# Tiny_Programmer_v11.net
KiCad netlist of a schematic drawn in EAGLE
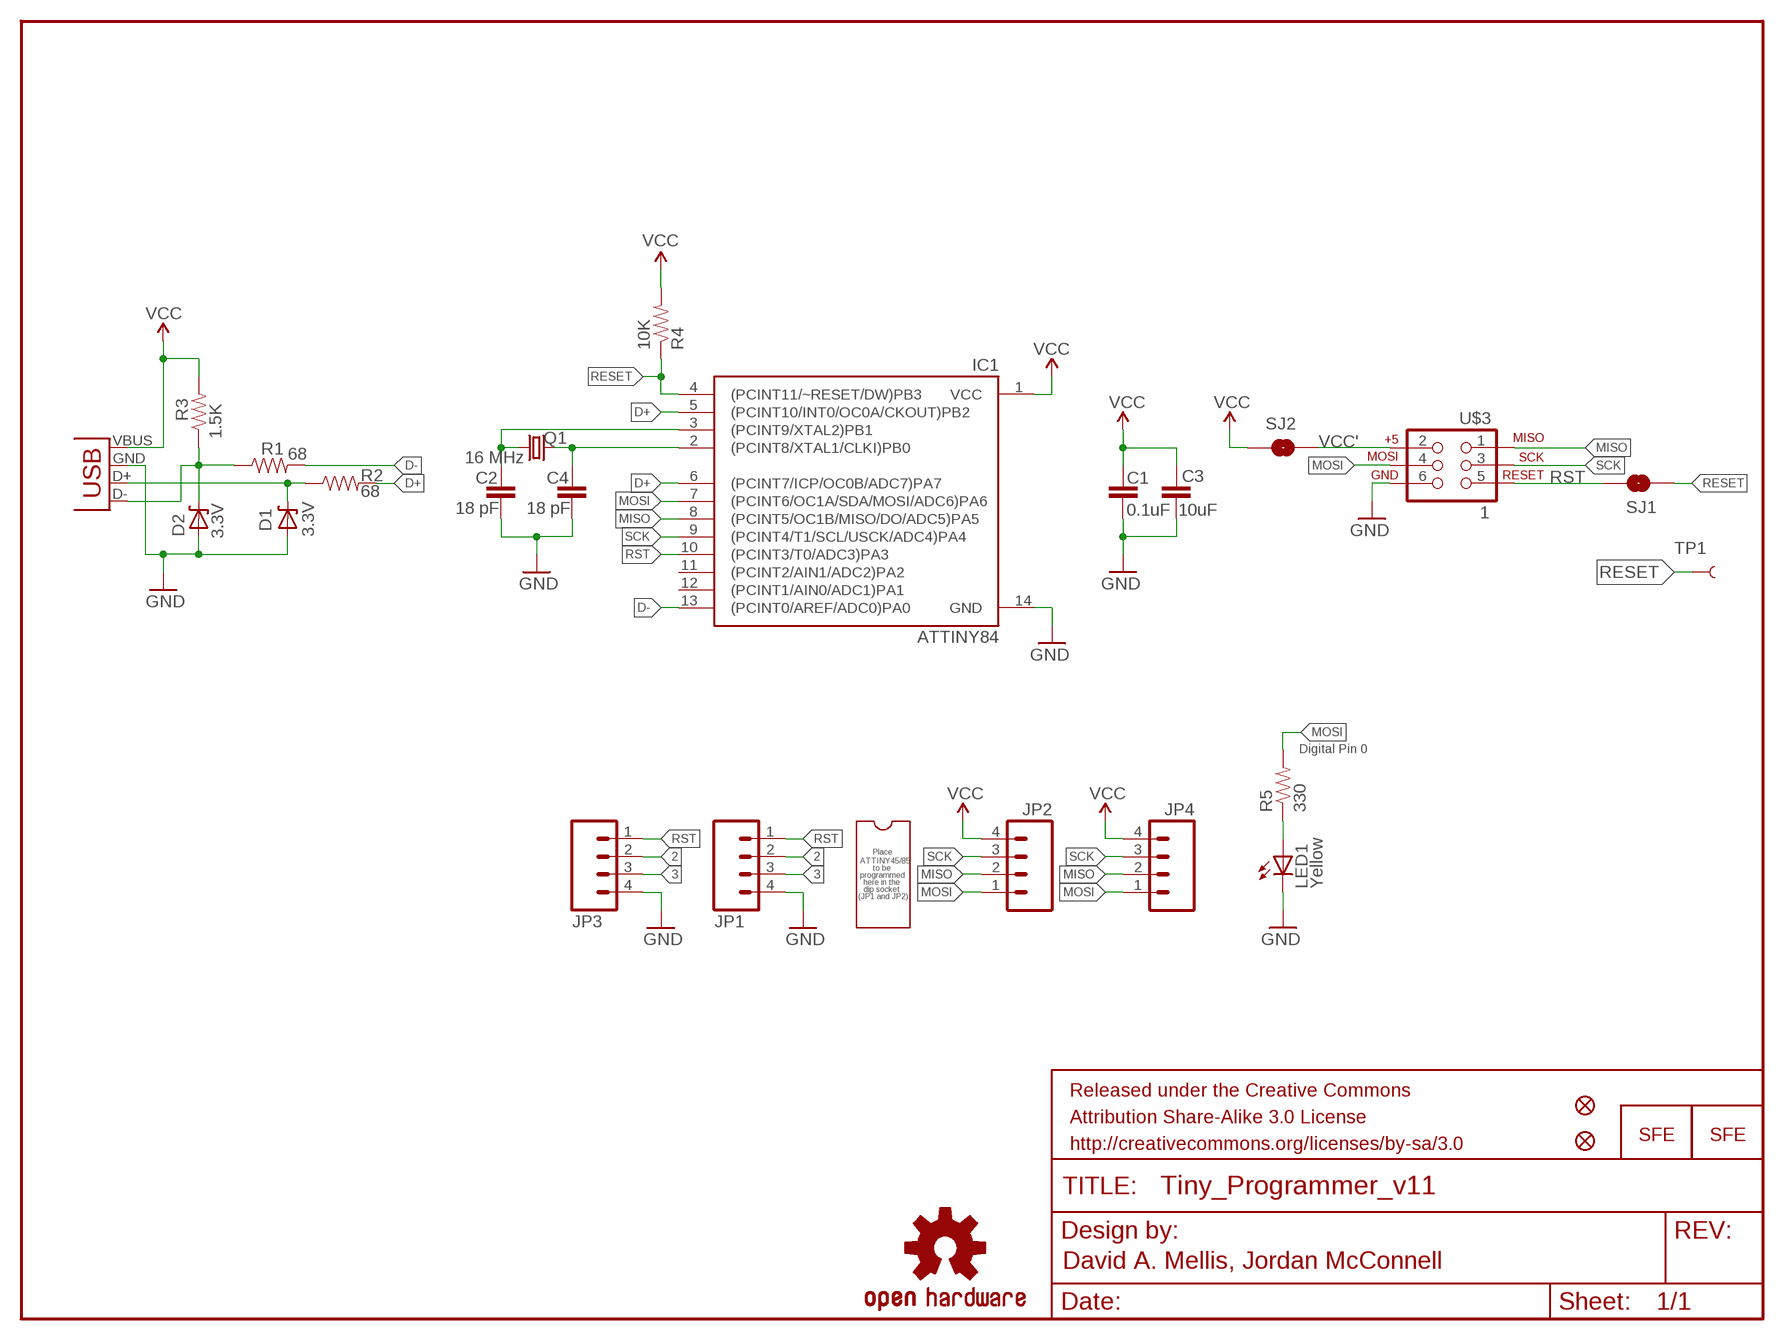
[diagram p0: schematic, sheet 1]

(export (version "E")
  (design (tool "Eeschema 10.0.6"))
  (components
    (comp (ref "C1")
      (value "0.1uF")
      (footprint "eagle-import:0402-CAP")
      (libsource (lib "eagle-import") (part "CAP0402-CAP"))
    )
    (comp (ref "C2")
      (value "18 pF")
      (footprint "eagle-import:0402-CAP")
      (libsource (lib "eagle-import") (part "CAP0402-CAP"))
    )
    (comp (ref "C3")
      (value "10uF")
      (footprint "eagle-import:0402-CAP")
      (libsource (lib "eagle-import") (part "CAP0402-CAP"))
    )
    (comp (ref "C4")
      (value "18 pF")
      (footprint "eagle-import:0402-CAP")
      (libsource (lib "eagle-import") (part "CAP0402-CAP"))
    )
    (comp (ref "D1")
      (value "3.3V")
      (footprint "eagle-import:SOD-323")
      (libsource (lib "eagle-import") (part "DIODE-ZENER-BZT52"))
    )
    (comp (ref "D2")
      (value "3.3V")
      (footprint "eagle-import:SOD-323")
      (libsource (lib "eagle-import") (part "DIODE-ZENER-BZT52"))
    )
    (comp (ref "FRAME1")
      (value "FRAME-LETTER")
      (footprint "eagle-import:CREATIVE_COMMONS")
      (libsource (lib "eagle-import") (part "FRAME-LETTER"))
    )
    (comp (ref "IC1")
      (value "ATTINY84")
      (footprint "eagle-import:SO14")
      (libsource (lib "eagle-import") (part "ATTINY84"))
    )
    (comp (ref "JP1")
      (value "M04PTH")
      (footprint "eagle-import:1X04")
      (libsource (lib "eagle-import") (part "M04PTH"))
    )
    (comp (ref "JP2")
      (value "M04PTH")
      (footprint "eagle-import:1X04")
      (libsource (lib "eagle-import") (part "M04PTH"))
    )
    (comp (ref "JP3")
      (value "M04SMD_STRAIGHT_COMBO")
      (footprint "eagle-import:1X04_SMD_STRAIGHT_COMBO")
      (libsource (lib "eagle-import") (part "M04SMD_STRAIGHT_COMBO"))
    )
    (comp (ref "JP4")
      (value "M04SMD_STRAIGHT_COMBO")
      (footprint "eagle-import:1X04_SMD_STRAIGHT_COMBO")
      (libsource (lib "eagle-import") (part "M04SMD_STRAIGHT_COMBO"))
    )
    (comp (ref "JP5")
      (value "LOGO-SFENEW")
      (footprint "eagle-import:SFE-NEW-WEBLOGO")
      (libsource (lib "eagle-import") (part "LOGO-SFENEW"))
    )
    (comp (ref "JP6")
      (value "LOGO-SFESK")
      (footprint "eagle-import:SFE-LOGO-FLAME")
      (libsource (lib "eagle-import") (part "LOGO-SFESK"))
    )
    (comp (ref "JP7")
      (value "FIDUCIALUFIDUCIAL")
      (footprint "eagle-import:MICRO-FIDUCIAL")
      (libsource (lib "eagle-import") (part "FIDUCIALUFIDUCIAL"))
    )
    (comp (ref "JP8")
      (value "FIDUCIALUFIDUCIAL")
      (footprint "eagle-import:MICRO-FIDUCIAL")
      (libsource (lib "eagle-import") (part "FIDUCIALUFIDUCIAL"))
    )
    (comp (ref "LED1")
      (value "Yellow")
      (footprint "eagle-import:LED-0603")
      (libsource (lib "eagle-import") (part "LED0603"))
    )
    (comp (ref "Q1")
      (value "16 MHz")
      (footprint "eagle-import:CRYSTAL-SMD-5X3")
      (libsource (lib "eagle-import") (part "CRYSTAL5X3"))
    )
    (comp (ref "R1")
      (value "68")
      (footprint "eagle-import:0402-RES")
      (libsource (lib "eagle-import") (part "RESISTOR0402-RES"))
    )
    (comp (ref "R2")
      (value "68")
      (footprint "eagle-import:0402-RES")
      (libsource (lib "eagle-import") (part "RESISTOR0402-RES"))
    )
    (comp (ref "R3")
      (value "1.5K")
      (footprint "eagle-import:0402-RES")
      (libsource (lib "eagle-import") (part "RESISTOR0402-RES"))
    )
    (comp (ref "R4")
      (value "10K")
      (footprint "eagle-import:0402-RES")
      (libsource (lib "eagle-import") (part "RESISTOR0402-RES"))
    )
    (comp (ref "R5")
      (value "330")
      (footprint "eagle-import:0402-RES")
      (libsource (lib "eagle-import") (part "RESISTOR0402-RES"))
    )
    (comp (ref "SJ1")
      (value "SOLDERJUMPERNO")
      (footprint "eagle-import:SJ_2S-NO")
      (libsource (lib "eagle-import") (part "SOLDERJUMPERNO"))
    )
    (comp (ref "SJ2")
      (value "SOLDERJUMPERNC")
      (footprint "eagle-import:SJ_2S")
      (libsource (lib "eagle-import") (part "SOLDERJUMPERNC"))
    )
    (comp (ref "TP1")
      (value "TEST-POINT3")
      (footprint "eagle-import:PAD.03X.03")
      (libsource (lib "eagle-import") (part "TEST-POINT3"))
    )
    (comp (ref "U$1")
      (value "OSHW-LOGOS")
      (footprint "eagle-import:OSHW-LOGO-S")
      (libsource (lib "eagle-import") (part "OSHW-LOGOS"))
    )
    (comp (ref "U$3")
      (value "1")
      (footprint "eagle-import:2X3")
      (libsource (lib "eagle-import") (part "AVR_SPI_PRG_6PTH"))
    )
    (comp (ref "X1")
      (value "USB-A-H")
      (footprint "eagle-import:USB-A-H")
      (libsource (lib "eagle-import") (part "USB-A-H"))
    )
  )
  (nets
    (net (code "1") (name "/VCC'") (class "Default")
      (node (ref "SJ2") (pin "2") (pinfunction "2_2") (pintype "passive"))
      (node (ref "U$3") (pin "2") (pinfunction "2_2") (pintype "passive"))
    )
    (net (code "2") (name "2") (class "Default")
      (node (ref "JP1") (pin "2") (pinfunction "2_2") (pintype "passive"))
      (node (ref "JP3") (pin "2") (pinfunction "2_2") (pintype "passive"))
    )
    (net (code "3") (name "3") (class "Default")
      (node (ref "JP1") (pin "3") (pinfunction "3_3") (pintype "passive"))
      (node (ref "JP3") (pin "3") (pinfunction "3_3") (pintype "passive"))
    )
    (net (code "4") (name "D+") (class "Default")
      (node (ref "IC1") (pin "5") (pinfunction "(PCINT10/INT0/OC0A/CKOUT)PB2_5") (pintype "bidirectional"))
      (node (ref "IC1") (pin "6") (pinfunction "(PCINT7/ICP/OC0B/ADC7)PA7_6") (pintype "bidirectional"))
      (node (ref "R2") (pin "2") (pinfunction "2_2") (pintype "passive"))
    )
    (net (code "5") (name "D-") (class "Default")
      (node (ref "IC1") (pin "13") (pinfunction "(PCINT0/AREF/ADC0)PA0_13") (pintype "bidirectional"))
      (node (ref "R1") (pin "2") (pinfunction "2_2") (pintype "passive"))
    )
    (net (code "6") (name "GND") (class "Default")
      (node (ref "C1") (pin "2") (pinfunction "2_2") (pintype "passive"))
      (node (ref "C2") (pin "2") (pinfunction "2_2") (pintype "passive"))
      (node (ref "C3") (pin "2") (pinfunction "2_2") (pintype "passive"))
      (node (ref "C4") (pin "2") (pinfunction "2_2") (pintype "passive"))
      (node (ref "D1") (pin "2") (pinfunction "A_2") (pintype "passive"))
      (node (ref "D2") (pin "2") (pinfunction "A_2") (pintype "passive"))
      (node (ref "IC1") (pin "14") (pinfunction "GND_14") (pintype "bidirectional"))
      (node (ref "JP1") (pin "4") (pinfunction "4_4") (pintype "passive"))
      (node (ref "JP3") (pin "4") (pinfunction "4_4") (pintype "passive"))
      (node (ref "LED1") (pin "C") (pinfunction "C_C") (pintype "passive"))
      (node (ref "U$3") (pin "6") (pinfunction "6_6") (pintype "passive"))
      (node (ref "X1") (pin "GND") (pinfunction "VBUS_GND") (pintype "bidirectional"))
    )
    (net (code "7") (name "MISO") (class "Default")
      (node (ref "IC1") (pin "8") (pinfunction "(PCINT5/OC1B/MISO/DO/ADC5)PA5_8") (pintype "bidirectional"))
      (node (ref "JP2") (pin "2") (pinfunction "2_2") (pintype "passive"))
      (node (ref "JP4") (pin "2") (pinfunction "2_2") (pintype "passive"))
      (node (ref "U$3") (pin "1") (pinfunction "1_1") (pintype "passive"))
    )
    (net (code "8") (name "MOSI") (class "Default")
      (node (ref "IC1") (pin "7") (pinfunction "(PCINT6/OC1A/SDA/MOSI/ADC6)PA6_7") (pintype "bidirectional"))
      (node (ref "JP2") (pin "1") (pinfunction "1_1") (pintype "passive"))
      (node (ref "JP4") (pin "1") (pinfunction "1_1") (pintype "passive"))
      (node (ref "R5") (pin "2") (pinfunction "2_2") (pintype "passive"))
      (node (ref "U$3") (pin "4") (pinfunction "4_4") (pintype "passive"))
    )
    (net (code "9") (name "Net-(D1-C)") (class "Default")
      (node (ref "D1") (pin "1") (pinfunction "C_1") (pintype "passive"))
      (node (ref "R2") (pin "1") (pinfunction "1_1") (pintype "passive"))
      (node (ref "X1") (pin "D+") (pinfunction "D-_D+") (pintype "bidirectional"))
    )
    (net (code "10") (name "Net-(D2-C)") (class "Default")
      (node (ref "D2") (pin "1") (pinfunction "C_1") (pintype "passive"))
      (node (ref "R1") (pin "1") (pinfunction "1_1") (pintype "passive"))
      (node (ref "R3") (pin "1") (pinfunction "1_1") (pintype "passive"))
      (node (ref "X1") (pin "D-") (pinfunction "D+_D-") (pintype "bidirectional"))
    )
    (net (code "11") (name "Net-(IC1-(PCINT8{slash}XTAL1{slash}CLKI)PB0)") (class "Default")
      (node (ref "C4") (pin "1") (pinfunction "1_1") (pintype "passive"))
      (node (ref "IC1") (pin "2") (pinfunction "(PCINT8/XTAL1/CLKI)PB0_2") (pintype "bidirectional"))
      (node (ref "Q1") (pin "1") (pinfunction "1_1") (pintype "passive"))
    )
    (net (code "12") (name "Net-(IC1-(PCINT9{slash}XTAL2)PB1)") (class "Default")
      (node (ref "C2") (pin "1") (pinfunction "1_1") (pintype "passive"))
      (node (ref "IC1") (pin "3") (pinfunction "(PCINT9/XTAL2)PB1_3") (pintype "bidirectional"))
      (node (ref "Q1") (pin "3") (pinfunction "2_3") (pintype "passive"))
    )
    (net (code "13") (name "Net-(LED1-PadA)") (class "Default")
      (node (ref "LED1") (pin "A") (pinfunction "A_A") (pintype "passive"))
      (node (ref "R5") (pin "1") (pinfunction "1_1") (pintype "passive"))
    )
    (net (code "14") (name "RESET") (class "Default")
      (node (ref "IC1") (pin "4") (pinfunction "(PCINT11/~{RESET/DW})PB3_4") (pintype "bidirectional"))
      (node (ref "R4") (pin "1") (pinfunction "1_1") (pintype "passive"))
      (node (ref "SJ1") (pin "1") (pinfunction "1_1") (pintype "passive"))
      (node (ref "TP1") (pin "P$1") (pinfunction "1_P$1") (pintype "bidirectional"))
    )
    (net (code "15") (name "RST") (class "Default")
      (node (ref "IC1") (pin "10") (pinfunction "(PCINT3/T0/ADC3)PA3_10") (pintype "bidirectional"))
      (node (ref "JP1") (pin "1") (pinfunction "1_1") (pintype "passive"))
      (node (ref "JP3") (pin "1") (pinfunction "1_1") (pintype "passive"))
      (node (ref "SJ1") (pin "2") (pinfunction "2_2") (pintype "passive"))
      (node (ref "U$3") (pin "5") (pinfunction "5_5") (pintype "passive"))
    )
    (net (code "16") (name "SCK") (class "Default")
      (node (ref "IC1") (pin "9") (pinfunction "(PCINT4/T1/SCL/USCK/ADC4)PA4_9") (pintype "bidirectional"))
      (node (ref "JP2") (pin "3") (pinfunction "3_3") (pintype "passive"))
      (node (ref "JP4") (pin "3") (pinfunction "3_3") (pintype "passive"))
      (node (ref "U$3") (pin "3") (pinfunction "3_3") (pintype "passive"))
    )
    (net (code "17") (name "VCC") (class "Default")
      (node (ref "C1") (pin "1") (pinfunction "1_1") (pintype "passive"))
      (node (ref "C3") (pin "1") (pinfunction "1_1") (pintype "passive"))
      (node (ref "IC1") (pin "1") (pinfunction "VCC_1") (pintype "bidirectional"))
      (node (ref "JP2") (pin "4") (pinfunction "4_4") (pintype "passive"))
      (node (ref "JP4") (pin "4") (pinfunction "4_4") (pintype "passive"))
      (node (ref "R3") (pin "2") (pinfunction "2_2") (pintype "passive"))
      (node (ref "R4") (pin "2") (pinfunction "2_2") (pintype "passive"))
      (node (ref "SJ2") (pin "1") (pinfunction "1_1") (pintype "passive"))
      (node (ref "X1") (pin "VBUS") (pinfunction "GND_VBUS") (pintype "bidirectional"))
    )
    (net (code "18") (name "unconnected-(IC1-(PCINT1{slash}AIN0{slash}ADC1)PA1-Pad12)") (class "Default")
      (node (ref "IC1") (pin "12") (pinfunction "(PCINT1/AIN0/ADC1)PA1_12") (pintype "bidirectional"))
    )
    (net (code "19") (name "unconnected-(IC1-(PCINT2{slash}AIN1{slash}ADC2)PA2-Pad11)") (class "Default")
      (node (ref "IC1") (pin "11") (pinfunction "(PCINT2/AIN1/ADC2)PA2_11") (pintype "bidirectional"))
    )
  )
)
